# Sheet2.net
KiCad netlist of a schematic drawn in Altium Designer
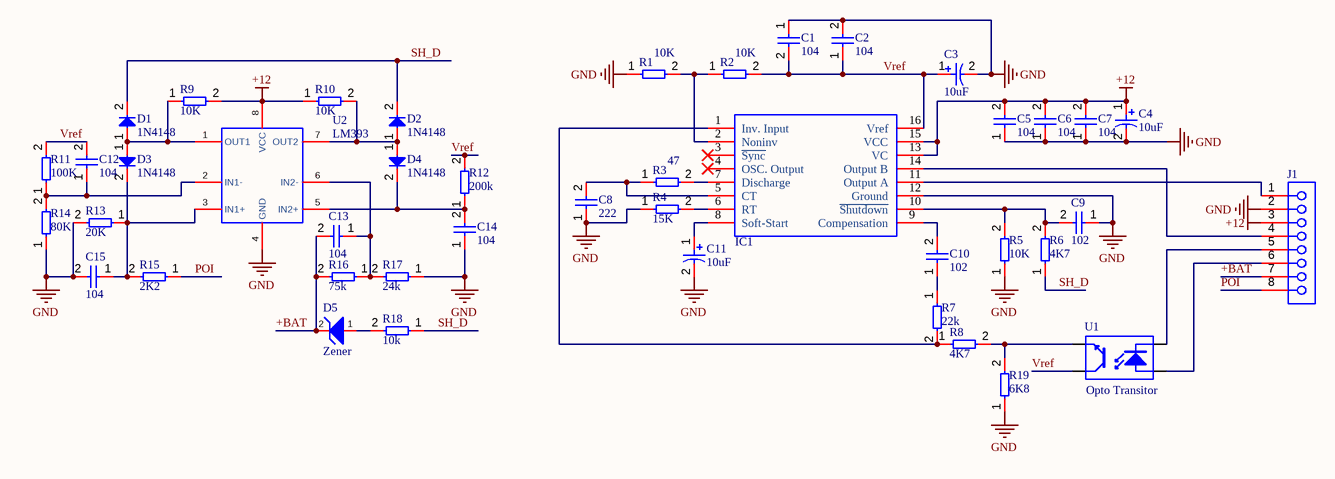
[diagram p0: Sheet2.SchDoc]

(export (version "E")
  (design (tool "Eeschema 10.0.6"))
  (components
    (comp (ref "C1") (value "104") (footprint "C0805") (libsource (lib "SMDLibrary") (part "C0805")))
    (comp (ref "C2") (value "104") (footprint "C0805") (libsource (lib "SMDLibrary") (part "C0805")))
    (comp (ref "C3")
      (value "10uF")
      (footprint "CAP_RAD_4mm")
      (libsource (lib "SMDLibrary") (part "Capacitor(Radian)"))
    )
    (comp (ref "C4")
      (value "10uF")
      (footprint "CAP_RAD_4mm")
      (libsource (lib "SMDLibrary") (part "Capacitor(Radian)"))
    )
    (comp (ref "C5") (value "104") (footprint "C0805") (libsource (lib "SMDLibrary") (part "C0805")))
    (comp (ref "C6") (value "104") (footprint "C0805") (libsource (lib "SMDLibrary") (part "C0805")))
    (comp (ref "C7") (value "104") (footprint "C0805") (libsource (lib "SMDLibrary") (part "C0805")))
    (comp (ref "C8") (value "222") (footprint "C0805") (libsource (lib "SMDLibrary") (part "C0805")))
    (comp (ref "C9") (value "102") (footprint "C0805") (libsource (lib "SMDLibrary") (part "C0805")))
    (comp (ref "C10") (value "102") (footprint "C0805") (libsource (lib "SMDLibrary") (part "C0805")))
    (comp (ref "C11")
      (value "10uF")
      (footprint "CAP_RAD_4mm")
      (libsource (lib "SMDLibrary") (part "Capacitor(Radian)"))
    )
    (comp (ref "C12") (value "104") (footprint "C0805") (libsource (lib "SMDLibrary") (part "C0805")))
    (comp (ref "C13") (value "104") (footprint "C0805") (libsource (lib "SMDLibrary") (part "C0805")))
    (comp (ref "C14") (value "104") (footprint "C0805") (libsource (lib "SMDLibrary") (part "C0805")))
    (comp (ref "C15") (value "104") (footprint "C0805") (libsource (lib "SMDLibrary") (part "C0805")))
    (comp (ref "D1")
      (value "1N4148")
      (footprint "SOD-80")
      (libsource (lib "SMDLibrary") (part "1N4148 (SOD-80)"))
    )
    (comp (ref "D2")
      (value "1N4148")
      (footprint "SOD-80")
      (libsource (lib "SMDLibrary") (part "1N4148 (SOD-80)"))
    )
    (comp (ref "D3")
      (value "1N4148")
      (footprint "SOD-80")
      (libsource (lib "SMDLibrary") (part "1N4148 (SOD-80)"))
    )
    (comp (ref "D4")
      (value "1N4148")
      (footprint "SOD-80")
      (libsource (lib "SMDLibrary") (part "1N4148 (SOD-80)"))
    )
    (comp (ref "D5")
      (value "Zener")
      (footprint "DO-213AB")
      (libsource (lib "SMDLibrary") (part "Diode Zener"))
    )
    (comp (ref "IC1")
      (value "Pulse width modulator control circuits")
      (footprint "SO16")
      (libsource (lib "SMDLibrary") (part "SG3525AN"))
    )
    (comp (ref "J1")
      (value "Header 8x1 TH Pitch 2.54mm")
      (footprint "Header 8x1 TH Pitch 2.54mm")
      (libsource (lib "SMDLibrary") (part "Header 8x1 TH Pitch 2.54mm"))
    )
    (comp (ref "R1") (value "10K") (footprint "R0805") (libsource (lib "") (part "Resistor SMD_3")))
    (comp (ref "R2") (value "10K") (footprint "R0805") (libsource (lib "") (part "Resistor SMD_3")))
    (comp (ref "R3") (value "47") (footprint "R0805") (libsource (lib "") (part "Resistor SMD_3")))
    (comp (ref "R4") (value "15K") (footprint "R0805") (libsource (lib "") (part "Resistor SMD_3")))
    (comp (ref "R5") (value "10K") (footprint "R0805") (libsource (lib "") (part "Resistor SMD_1")))
    (comp (ref "R6") (value "4K7") (footprint "R0805") (libsource (lib "") (part "Resistor SMD_1")))
    (comp (ref "R7") (value "22k") (footprint "R0805") (libsource (lib "") (part "Resistor SMD_2")))
    (comp (ref "R8") (value "4K7") (footprint "R0805") (libsource (lib "") (part "Resistor SMD_3")))
    (comp (ref "R9") (value "10K") (footprint "R0805") (libsource (lib "") (part "Resistor SMD_3")))
    (comp (ref "R10") (value "10K") (footprint "R0805") (libsource (lib "") (part "Resistor SMD_3")))
    (comp (ref "R11") (value "100K") (footprint "R0805") (libsource (lib "") (part "Resistor SMD_1")))
    (comp (ref "R12") (value "200k") (footprint "R0805") (libsource (lib "") (part "Resistor SMD_1")))
    (comp (ref "R13") (value "20K") (footprint "R0805") (libsource (lib "SMDLibrary") (part "Resistor SMD")))
    (comp (ref "R14") (value "80K") (footprint "R0805") (libsource (lib "") (part "Resistor SMD_1")))
    (comp (ref "R15") (value "2K2") (footprint "R0805") (libsource (lib "SMDLibrary") (part "Resistor SMD")))
    (comp (ref "R16") (value "75k") (footprint "R0805") (libsource (lib "SMDLibrary") (part "Resistor SMD")))
    (comp (ref "R17") (value "24k") (footprint "R0805") (libsource (lib "SMDLibrary") (part "Resistor SMD")))
    (comp (ref "R18") (value "10k") (footprint "R0805") (libsource (lib "SMDLibrary") (part "Resistor SMD")))
    (comp (ref "R19") (value "6K8") (footprint "R0805") (libsource (lib "") (part "Resistor SMD_1")))
    (comp (ref "U1")
      (value "Opto Transitor")
      (footprint "DIP 4")
      (fields (field (name "PUBLISHER") "Altium Limited"))
      (libsource (lib "Library 3D") (part "Opto Transitor"))
    )
    (comp (ref "U2")
      (value "LM393")
      (footprint "SOIC08_1.27_6.0")
      (libsource (lib "SMDLibrary") (part "LM393"))
    )
  )
  (nets
    (net (code "1") (name "+12") (class "Default")
      (node (ref "C4") (pin "1") (pinfunction "1_1") (pintype "passive"))
      (node (ref "C5") (pin "2") (pinfunction "2_2") (pintype "passive"))
      (node (ref "C6") (pin "2") (pinfunction "2_2") (pintype "passive"))
      (node (ref "C7") (pin "2") (pinfunction "2_2") (pintype "passive"))
      (node (ref "IC1") (pin "13") (pinfunction "VC_13") (pintype "passive"))
      (node (ref "IC1") (pin "15") (pinfunction "VCC_15") (pintype "passive"))
      (node (ref "J1") (pin "3") (pinfunction "3_3") (pintype "passive"))
      (node (ref "R10") (pin "1") (pinfunction "1_1") (pintype "passive"))
      (node (ref "R9") (pin "2") (pinfunction "2_2") (pintype "passive"))
      (node (ref "U2") (pin "8") (pinfunction "VCC_8") (pintype "passive"))
    )
    (net (code "2") (name "/+BAT") (class "Default")
      (node (ref "C13") (pin "2") (pinfunction "2_2") (pintype "passive"))
      (node (ref "D5") (pin "2") (pinfunction "K_2") (pintype "passive"))
      (node (ref "J1") (pin "7") (pinfunction "7_7") (pintype "passive"))
      (node (ref "R16") (pin "2") (pinfunction "2_2") (pintype "passive"))
    )
    (net (code "3") (name "/POI") (class "Default")
      (node (ref "J1") (pin "8") (pinfunction "8_8") (pintype "passive"))
      (node (ref "R15") (pin "1") (pinfunction "1_1") (pintype "passive"))
    )
    (net (code "4") (name "/SH_D") (class "Default")
      (node (ref "D1") (pin "2") (pinfunction "2_2") (pintype "passive"))
      (node (ref "D2") (pin "2") (pinfunction "2_2") (pintype "passive"))
      (node (ref "R18") (pin "1") (pinfunction "1_1") (pintype "passive"))
      (node (ref "R6") (pin "1") (pinfunction "1_1") (pintype "passive"))
    )
    (net (code "5") (name "/Vref") (class "Default")
      (node (ref "C1") (pin "2") (pinfunction "2_2") (pintype "passive"))
      (node (ref "C12") (pin "2") (pinfunction "2_2") (pintype "passive"))
      (node (ref "C2") (pin "1") (pinfunction "1_1") (pintype "passive"))
      (node (ref "C3") (pin "1") (pinfunction "1_1") (pintype "passive"))
      (node (ref "IC1") (pin "16") (pinfunction "Vref_16") (pintype "passive"))
      (node (ref "R11") (pin "2") (pinfunction "2_2") (pintype "passive"))
      (node (ref "R12") (pin "2") (pinfunction "2_2") (pintype "passive"))
      (node (ref "R2") (pin "2") (pinfunction "2_2") (pintype "passive"))
      (node (ref "U1") (pin "4") (pinfunction "C_4") (pintype "passive"))
    )
    (net (code "6") (name "GND") (class "Default")
      (node (ref "C1") (pin "1") (pinfunction "1_1") (pintype "passive"))
      (node (ref "C11") (pin "2") (pinfunction "2_2") (pintype "passive"))
      (node (ref "C14") (pin "1") (pinfunction "1_1") (pintype "passive"))
      (node (ref "C15") (pin "2") (pinfunction "2_2") (pintype "passive"))
      (node (ref "C2") (pin "2") (pinfunction "2_2") (pintype "passive"))
      (node (ref "C3") (pin "2") (pinfunction "2_2") (pintype "passive"))
      (node (ref "C4") (pin "2") (pinfunction "2_2") (pintype "passive"))
      (node (ref "C5") (pin "1") (pinfunction "1_1") (pintype "passive"))
      (node (ref "C6") (pin "1") (pinfunction "1_1") (pintype "passive"))
      (node (ref "C7") (pin "1") (pinfunction "1_1") (pintype "passive"))
      (node (ref "C8") (pin "1") (pinfunction "1_1") (pintype "passive"))
      (node (ref "C9") (pin "1") (pinfunction "1_1") (pintype "passive"))
      (node (ref "IC1") (pin "12") (pinfunction "Ground_12") (pintype "passive"))
      (node (ref "J1") (pin "2") (pinfunction "2_2") (pintype "passive"))
      (node (ref "R1") (pin "1") (pinfunction "1_1") (pintype "passive"))
      (node (ref "R13") (pin "2") (pinfunction "2_2") (pintype "passive"))
      (node (ref "R14") (pin "1") (pinfunction "1_1") (pintype "passive"))
      (node (ref "R17") (pin "1") (pinfunction "1_1") (pintype "passive"))
      (node (ref "R19") (pin "1") (pinfunction "1_1") (pintype "passive"))
      (node (ref "R4") (pin "1") (pinfunction "1_1") (pintype "passive"))
      (node (ref "R5") (pin "1") (pinfunction "1_1") (pintype "passive"))
      (node (ref "U2") (pin "4") (pinfunction "GND_4") (pintype "passive"))
    )
    (net (code "7") (name "Net-(C10-Pad1)") (class "Default")
      (node (ref "C10") (pin "1") (pinfunction "1_1") (pintype "passive"))
      (node (ref "R7") (pin "1") (pinfunction "1_1") (pintype "passive"))
    )
    (net (code "8") (name "Net-(D5-A)") (class "Default")
      (node (ref "D5") (pin "1") (pinfunction "A_1") (pintype "passive"))
      (node (ref "R18") (pin "2") (pinfunction "2_2") (pintype "passive"))
    )
    (net (code "9") (name "Net-(IC1-CT)") (class "Default")
      (node (ref "C8") (pin "2") (pinfunction "2_2") (pintype "passive"))
      (node (ref "IC1") (pin "5") (pinfunction "CT_5") (pintype "passive"))
      (node (ref "R3") (pin "1") (pinfunction "1_1") (pintype "passive"))
    )
    (net (code "10") (name "Net-(IC1-Compensation)") (class "Default")
      (node (ref "C10") (pin "2") (pinfunction "2_2") (pintype "passive"))
      (node (ref "IC1") (pin "9") (pinfunction "Compensation_9") (pintype "passive"))
    )
    (net (code "11") (name "Net-(IC1-Discharge)") (class "Default")
      (node (ref "IC1") (pin "7") (pinfunction "Discharge_7") (pintype "passive"))
      (node (ref "R3") (pin "2") (pinfunction "2_2") (pintype "passive"))
    )
    (net (code "12") (name "Net-(IC1-Inv._Input)") (class "Default")
      (node (ref "IC1") (pin "1") (pinfunction "Inv._Input_1") (pintype "passive"))
      (node (ref "R7") (pin "2") (pinfunction "2_2") (pintype "passive"))
      (node (ref "R8") (pin "1") (pinfunction "1_1") (pintype "passive"))
    )
    (net (code "13") (name "Net-(IC1-Noninv)") (class "Default")
      (node (ref "IC1") (pin "2") (pinfunction "Noninv_2") (pintype "passive"))
      (node (ref "R1") (pin "2") (pinfunction "2_2") (pintype "passive"))
      (node (ref "R2") (pin "1") (pinfunction "1_1") (pintype "passive"))
    )
    (net (code "14") (name "Net-(IC1-Output_A)") (class "Default")
      (node (ref "IC1") (pin "11") (pinfunction "Output_A_11") (pintype "passive"))
      (node (ref "J1") (pin "1") (pinfunction "1_1") (pintype "passive"))
    )
    (net (code "15") (name "Net-(IC1-Output_B)") (class "Default")
      (node (ref "IC1") (pin "14") (pinfunction "Output_B_14") (pintype "passive"))
      (node (ref "J1") (pin "4") (pinfunction "4_4") (pintype "passive"))
    )
    (net (code "16") (name "Net-(IC1-RT)") (class "Default")
      (node (ref "IC1") (pin "6") (pinfunction "RT_6") (pintype "passive"))
      (node (ref "R4") (pin "2") (pinfunction "2_2") (pintype "passive"))
    )
    (net (code "17") (name "Net-(IC1-Soft-Start)") (class "Default")
      (node (ref "C11") (pin "1") (pinfunction "1_1") (pintype "passive"))
      (node (ref "IC1") (pin "8") (pinfunction "Soft-Start_8") (pintype "passive"))
    )
    (net (code "18") (name "Net-(IC1-~{Shutdown})") (class "Default")
      (node (ref "C9") (pin "2") (pinfunction "2_2") (pintype "passive"))
      (node (ref "IC1") (pin "10") (pinfunction "~{Shutdown}_10") (pintype "passive"))
      (node (ref "R5") (pin "2") (pinfunction "2_2") (pintype "passive"))
      (node (ref "R6") (pin "2") (pinfunction "2_2") (pintype "passive"))
    )
    (net (code "19") (name "Net-(U1-A)") (class "Default")
      (node (ref "J1") (pin "6") (pinfunction "6_6") (pintype "passive"))
      (node (ref "U1") (pin "1") (pinfunction "A_1") (pintype "passive"))
    )
    (net (code "20") (name "Net-(U1-E)") (class "Default")
      (node (ref "R19") (pin "2") (pinfunction "2_2") (pintype "passive"))
      (node (ref "R8") (pin "2") (pinfunction "2_2") (pintype "passive"))
      (node (ref "U1") (pin "3") (pinfunction "E_3") (pintype "passive"))
    )
    (net (code "21") (name "Net-(U1-K)") (class "Default")
      (node (ref "J1") (pin "5") (pinfunction "5_5") (pintype "passive"))
      (node (ref "U1") (pin "2") (pinfunction "K_2") (pintype "passive"))
    )
    (net (code "22") (name "Net-(U2-IN1+)") (class "Default")
      (node (ref "C15") (pin "1") (pinfunction "1_1") (pintype "passive"))
      (node (ref "D3") (pin "2") (pinfunction "2_2") (pintype "passive"))
      (node (ref "R13") (pin "1") (pinfunction "1_1") (pintype "passive"))
      (node (ref "R15") (pin "2") (pinfunction "2_2") (pintype "passive"))
      (node (ref "U2") (pin "3") (pinfunction "IN1+_3") (pintype "passive"))
    )
    (net (code "23") (name "Net-(U2-IN1-)") (class "Default")
      (node (ref "C12") (pin "1") (pinfunction "1_1") (pintype "passive"))
      (node (ref "R11") (pin "1") (pinfunction "1_1") (pintype "passive"))
      (node (ref "R14") (pin "2") (pinfunction "2_2") (pintype "passive"))
      (node (ref "U2") (pin "2") (pinfunction "IN1-_2") (pintype "passive"))
    )
    (net (code "24") (name "Net-(U2-IN2+)") (class "Default")
      (node (ref "C14") (pin "2") (pinfunction "2_2") (pintype "passive"))
      (node (ref "D4") (pin "2") (pinfunction "2_2") (pintype "passive"))
      (node (ref "R12") (pin "1") (pinfunction "1_1") (pintype "passive"))
      (node (ref "U2") (pin "5") (pinfunction "IN2+_5") (pintype "passive"))
    )
    (net (code "25") (name "Net-(U2-IN2-)") (class "Default")
      (node (ref "C13") (pin "1") (pinfunction "1_1") (pintype "passive"))
      (node (ref "R16") (pin "1") (pinfunction "1_1") (pintype "passive"))
      (node (ref "R17") (pin "2") (pinfunction "2_2") (pintype "passive"))
      (node (ref "U2") (pin "6") (pinfunction "IN2-_6") (pintype "passive"))
    )
    (net (code "26") (name "Net-(U2-OUT1)") (class "Default")
      (node (ref "D1") (pin "1") (pinfunction "1_1") (pintype "passive"))
      (node (ref "D3") (pin "1") (pinfunction "1_1") (pintype "passive"))
      (node (ref "R9") (pin "1") (pinfunction "1_1") (pintype "passive"))
      (node (ref "U2") (pin "1") (pinfunction "OUT1_1") (pintype "passive"))
    )
    (net (code "27") (name "Net-(U2-OUT2)") (class "Default")
      (node (ref "D2") (pin "1") (pinfunction "1_1") (pintype "passive"))
      (node (ref "D4") (pin "1") (pinfunction "1_1") (pintype "passive"))
      (node (ref "R10") (pin "2") (pinfunction "2_2") (pintype "passive"))
      (node (ref "U2") (pin "7") (pinfunction "OUT2_7") (pintype "passive"))
    )
    (net (code "28") (name "unconnected-(IC1-OSC._Output-Pad4)") (class "Default")
      (node (ref "IC1") (pin "4") (pinfunction "OSC._Output_4") (pintype "passive+no_connect"))
    )
    (net (code "29") (name "unconnected-(IC1-~{Sync}-Pad3)") (class "Default")
      (node (ref "IC1") (pin "3") (pinfunction "~{Sync}_3") (pintype "passive+no_connect"))
    )
  )
)
